# miniprot.net
KiCad netlist of a schematic drawn in EAGLE
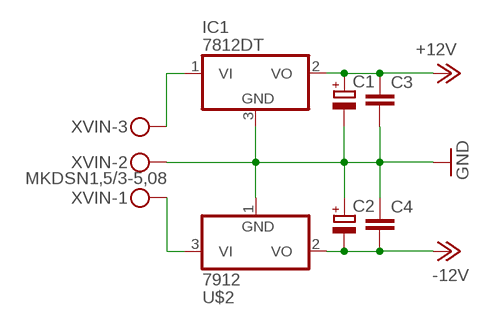
[diagram p0: schematic, sheet 1]
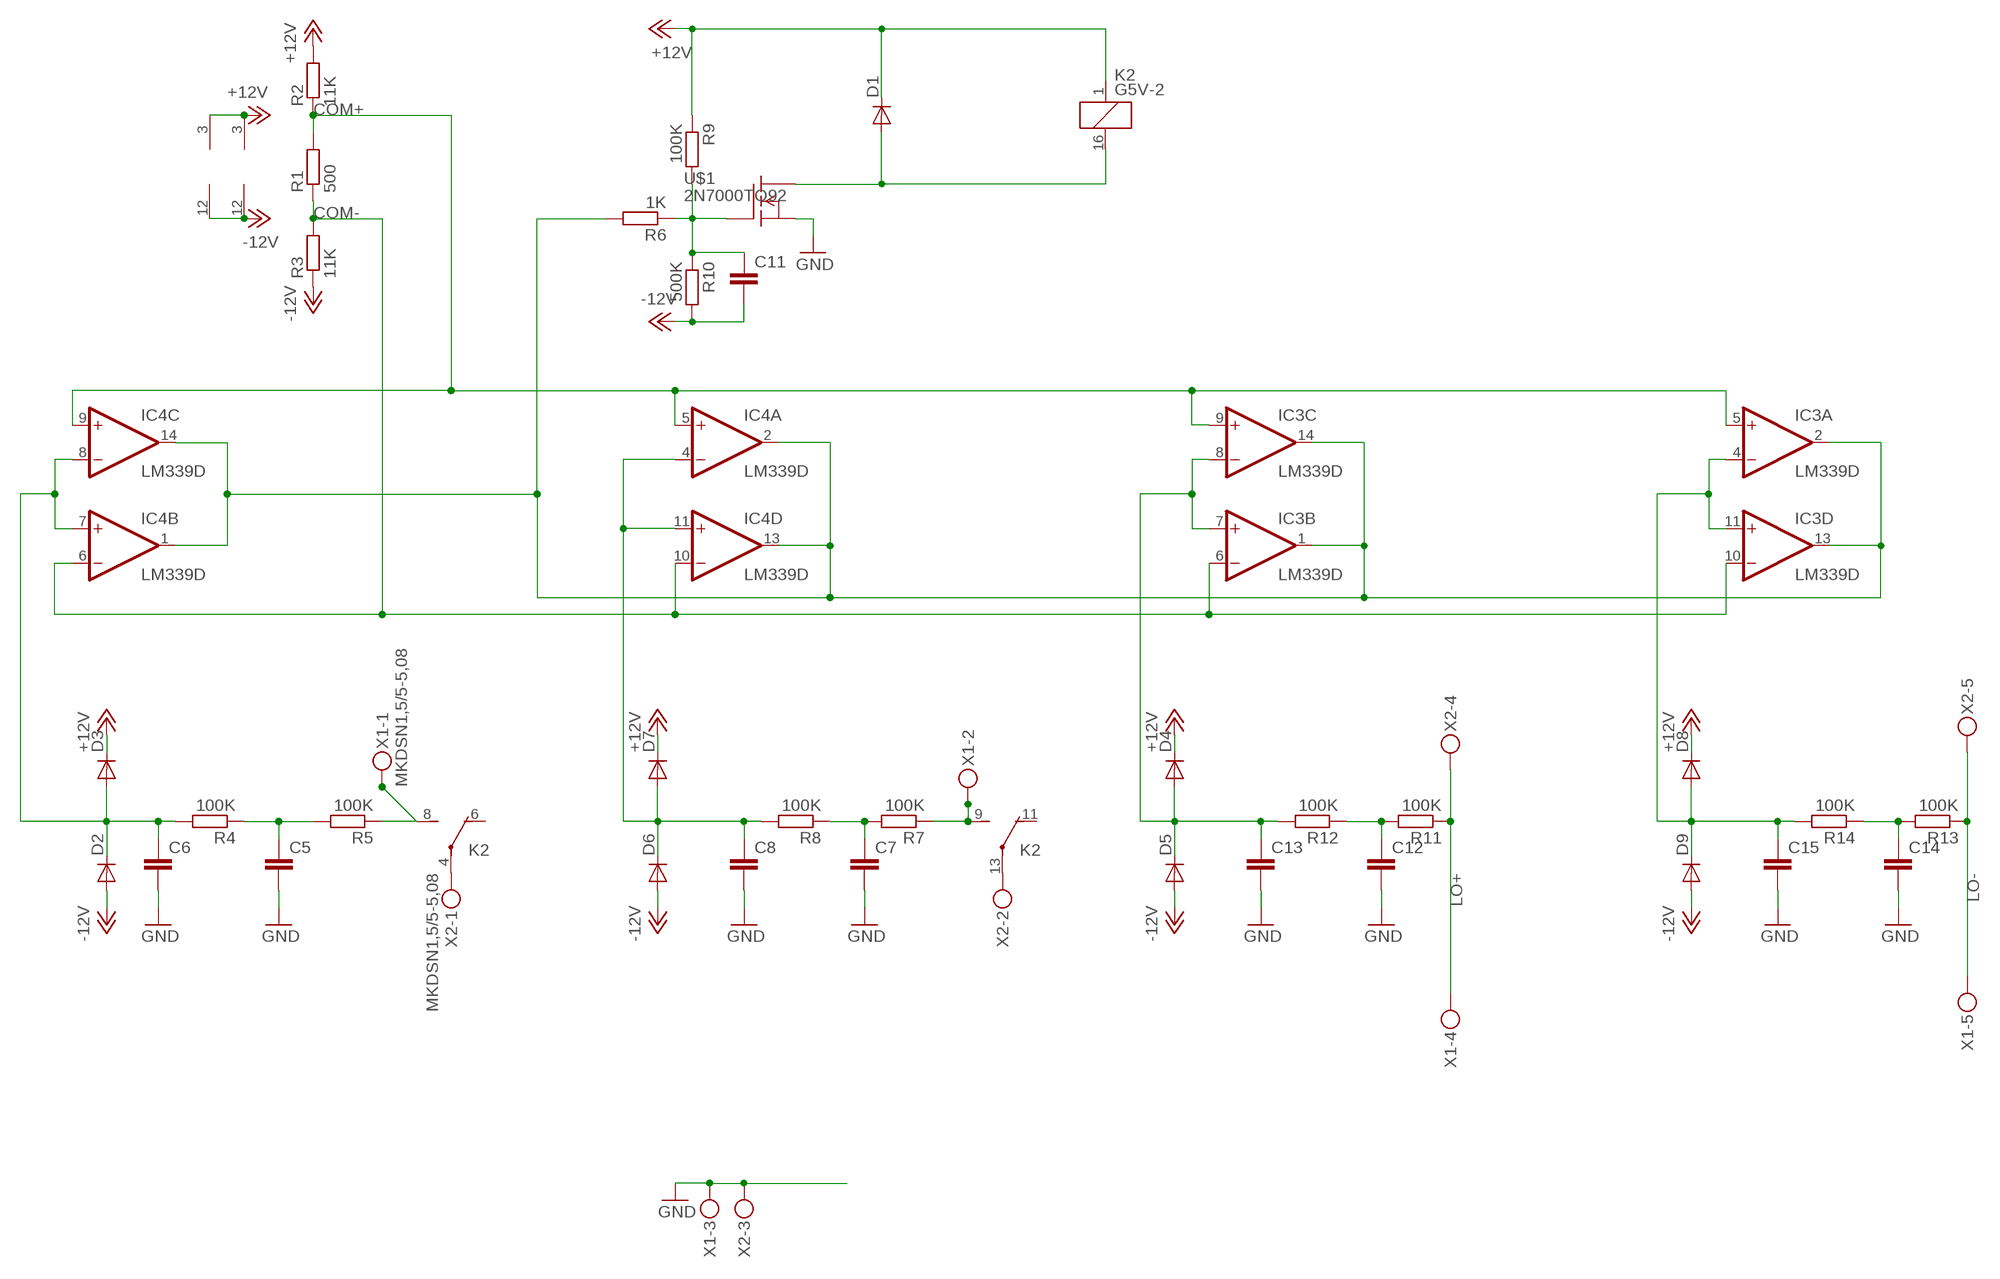
[diagram p1: schematic, sheet 2]

(export (version "E")
  (design (tool "Eeschema 10.0.6"))
  (components
    (comp (ref "C5")
      (value "C-EUC0805")
      (footprint "eagle-import:C0805")
      (libsource (lib "eagle-import") (part "C-EUC0805"))
    )
    (comp (ref "C6")
      (value "C-EUC0805")
      (footprint "eagle-import:C0805")
      (libsource (lib "eagle-import") (part "C-EUC0805"))
    )
    (comp (ref "C7")
      (value "C-EUC0805")
      (footprint "eagle-import:C0805")
      (libsource (lib "eagle-import") (part "C-EUC0805"))
    )
    (comp (ref "C8")
      (value "C-EUC0805")
      (footprint "eagle-import:C0805")
      (libsource (lib "eagle-import") (part "C-EUC0805"))
    )
    (comp (ref "C11")
      (value "C-EUC1210")
      (footprint "eagle-import:C1210")
      (libsource (lib "eagle-import") (part "C-EUC1210"))
    )
    (comp (ref "C12")
      (value "C-EUC0805")
      (footprint "eagle-import:C0805")
      (libsource (lib "eagle-import") (part "C-EUC0805"))
    )
    (comp (ref "C13")
      (value "C-EUC0805")
      (footprint "eagle-import:C0805")
      (libsource (lib "eagle-import") (part "C-EUC0805"))
    )
    (comp (ref "C14")
      (value "C-EUC0805")
      (footprint "eagle-import:C0805")
      (libsource (lib "eagle-import") (part "C-EUC0805"))
    )
    (comp (ref "C15")
      (value "C-EUC0805")
      (footprint "eagle-import:C0805")
      (libsource (lib "eagle-import") (part "C-EUC0805"))
    )
    (comp (ref "D1")
      (value "DIODE-DO214AC")
      (footprint "eagle-import:DO214AC")
      (libsource (lib "eagle-import") (part "DIODE-DO214AC"))
    )
    (comp (ref "D2")
      (value "DIODE-SOD80C")
      (footprint "eagle-import:SOD80C")
      (libsource (lib "eagle-import") (part "DIODE-SOD80C"))
    )
    (comp (ref "D3")
      (value "DIODE-SOD80C")
      (footprint "eagle-import:SOD80C")
      (libsource (lib "eagle-import") (part "DIODE-SOD80C"))
    )
    (comp (ref "D4")
      (value "DIODE-SOD80C")
      (footprint "eagle-import:SOD80C")
      (libsource (lib "eagle-import") (part "DIODE-SOD80C"))
    )
    (comp (ref "D5")
      (value "DIODE-SOD80C")
      (footprint "eagle-import:SOD80C")
      (libsource (lib "eagle-import") (part "DIODE-SOD80C"))
    )
    (comp (ref "D6")
      (value "DIODE-SOD80C")
      (footprint "eagle-import:SOD80C")
      (libsource (lib "eagle-import") (part "DIODE-SOD80C"))
    )
    (comp (ref "D7")
      (value "DIODE-SOD80C")
      (footprint "eagle-import:SOD80C")
      (libsource (lib "eagle-import") (part "DIODE-SOD80C"))
    )
    (comp (ref "D8")
      (value "DIODE-SOD80C")
      (footprint "eagle-import:SOD80C")
      (libsource (lib "eagle-import") (part "DIODE-SOD80C"))
    )
    (comp (ref "D9")
      (value "DIODE-SOD80C")
      (footprint "eagle-import:SOD80C")
      (libsource (lib "eagle-import") (part "DIODE-SOD80C"))
    )
    (comp (ref "IC3")
      (value "LM339D")
      (footprint "eagle-import:SO14")
      (libsource (lib "eagle-import") (part "LM339D"))
    )
    (comp (ref "IC4")
      (value "LM339D")
      (footprint "eagle-import:SO14")
      (libsource (lib "eagle-import") (part "linear_262_LM339D"))
    )
    (comp (ref "K2")
      (value "G5V-2")
      (footprint "eagle-import:G5V-2")
      (fields (field (name "MPN") "G5V-2 5DC"))
      (libsource (lib "eagle-import") (part "G5V-2"))
    )
    (comp (ref "R1")
      (value "500")
      (footprint "eagle-import:R0805")
      (libsource (lib "eagle-import") (part "R-EU_R0805"))
    )
    (comp (ref "R2")
      (value "11K")
      (footprint "eagle-import:R0805")
      (libsource (lib "eagle-import") (part "R-EU_R0805"))
    )
    (comp (ref "R3")
      (value "11K")
      (footprint "eagle-import:R0805")
      (libsource (lib "eagle-import") (part "R-EU_R0805"))
    )
    (comp (ref "R4")
      (value "100K")
      (footprint "eagle-import:R0805")
      (libsource (lib "eagle-import") (part "R-EU_R0805"))
    )
    (comp (ref "R5")
      (value "100K")
      (footprint "eagle-import:R0805")
      (libsource (lib "eagle-import") (part "R-EU_R0805"))
    )
    (comp (ref "R6")
      (value "1K")
      (footprint "eagle-import:R0805")
      (libsource (lib "eagle-import") (part "R-EU_R0805"))
    )
    (comp (ref "R7")
      (value "100K")
      (footprint "eagle-import:R0805")
      (libsource (lib "eagle-import") (part "R-EU_R0805"))
    )
    (comp (ref "R8")
      (value "100K")
      (footprint "eagle-import:R0805")
      (libsource (lib "eagle-import") (part "R-EU_R0805"))
    )
    (comp (ref "R9")
      (value "100K")
      (footprint "eagle-import:R0805")
      (libsource (lib "eagle-import") (part "R-EU_R0805"))
    )
    (comp (ref "R10")
      (value "500K")
      (footprint "eagle-import:R0805")
      (libsource (lib "eagle-import") (part "R-EU_R0805"))
    )
    (comp (ref "R11")
      (value "100K")
      (footprint "eagle-import:R0805")
      (libsource (lib "eagle-import") (part "R-EU_R0805"))
    )
    (comp (ref "R12")
      (value "100K")
      (footprint "eagle-import:R0805")
      (libsource (lib "eagle-import") (part "R-EU_R0805"))
    )
    (comp (ref "R13")
      (value "100K")
      (footprint "eagle-import:R0805")
      (libsource (lib "eagle-import") (part "R-EU_R0805"))
    )
    (comp (ref "R14")
      (value "100K")
      (footprint "eagle-import:R0805")
      (libsource (lib "eagle-import") (part "R-EU_R0805"))
    )
    (comp (ref "U$1")
      (value "2N7000TO92")
      (footprint "eagle-import:TO92-")
      (libsource (lib "eagle-import") (part "2N7000TO92"))
    )
    (comp (ref "X1")
      (value "MKDSN1,5/5-5,08")
      (footprint "eagle-import:MKDSN1,5_5-5,08")
      (libsource (lib "eagle-import") (part "MKDSN1,5/5-5,08"))
    )
    (comp (ref "X2")
      (value "MKDSN1,5/5-5,08")
      (footprint "eagle-import:MKDSN1,5_5-5,08")
      (libsource (lib "eagle-import") (part "MKDSN1,5/5-5,08"))
    )
    (comp (ref "C1")
      (value "CPOL-EUE2.5-7")
      (footprint "eagle-import:E2,5-7")
      (libsource (lib "eagle-import") (part "CPOL-EUE2.5-7"))
    )
    (comp (ref "C2")
      (value "CPOL-EUE2.5-7")
      (footprint "eagle-import:E2,5-7")
      (libsource (lib "eagle-import") (part "CPOL-EUE2.5-7"))
    )
    (comp (ref "C3")
      (value "C-EUC0805")
      (footprint "eagle-import:C0805")
      (libsource (lib "eagle-import") (part "C-EUC0805"))
    )
    (comp (ref "C4")
      (value "C-EUC0805")
      (footprint "eagle-import:C0805")
      (libsource (lib "eagle-import") (part "C-EUC0805"))
    )
    (comp (ref "IC1")
      (value "7812DT")
      (footprint "eagle-import:TO252")
      (libsource (lib "eagle-import") (part "78DT12"))
    )
    (comp (ref "U$2")
      (value "7912")
      (footprint "eagle-import:TO252")
      (libsource (lib "eagle-import") (part "7912"))
    )
    (comp (ref "XVIN")
      (value "MKDSN1,5/3-5,08")
      (footprint "eagle-import:MKDSN1,5_3-5,08")
      (libsource (lib "eagle-import") (part "MKDSN1,5/3-5,08"))
    )
  )
  (nets
    (net (code "1") (name "+12V") (class "Default")
      (node (ref "C1") (pin "+") (pinfunction "+_+") (pintype "passive"))
      (node (ref "C3") (pin "1") (pinfunction "1_1") (pintype "passive"))
      (node (ref "D1") (pin "C") (pinfunction "C_C") (pintype "passive"))
      (node (ref "D3") (pin "C") (pinfunction "C_C") (pintype "passive"))
      (node (ref "D4") (pin "C") (pinfunction "C_C") (pintype "passive"))
      (node (ref "D7") (pin "C") (pinfunction "C_C") (pintype "passive"))
      (node (ref "D8") (pin "C") (pinfunction "C_C") (pintype "passive"))
      (node (ref "IC1") (pin "2") (pinfunction "VO_2") (pintype "passive"))
      (node (ref "IC3") (pin "3") (pinfunction "V+_3") (pintype "power_in"))
      (node (ref "IC4") (pin "3") (pinfunction "V+_3") (pintype "power_in"))
      (node (ref "K2") (pin "1") (pinfunction "1_1") (pintype "passive"))
      (node (ref "R2") (pin "2") (pinfunction "2_2") (pintype "passive"))
      (node (ref "R9") (pin "1") (pinfunction "1_1") (pintype "passive"))
    )
    (net (code "2") (name "-12V") (class "Default")
      (node (ref "C11") (pin "2") (pinfunction "2_2") (pintype "passive"))
      (node (ref "C2") (pin "-") (pinfunction "-_-") (pintype "passive"))
      (node (ref "C4") (pin "2") (pinfunction "2_2") (pintype "passive"))
      (node (ref "D2") (pin "A") (pinfunction "A_A") (pintype "passive"))
      (node (ref "D5") (pin "A") (pinfunction "A_A") (pintype "passive"))
      (node (ref "D6") (pin "A") (pinfunction "A_A") (pintype "passive"))
      (node (ref "D9") (pin "A") (pinfunction "A_A") (pintype "passive"))
      (node (ref "IC3") (pin "12") (pinfunction "GND_12") (pintype "power_in"))
      (node (ref "IC4") (pin "12") (pinfunction "GND_12") (pintype "power_in"))
      (node (ref "R10") (pin "2") (pinfunction "2_2") (pintype "passive"))
      (node (ref "R3") (pin "1") (pinfunction "1_1") (pintype "passive"))
      (node (ref "U$2") (pin "2") (pinfunction "VO_2") (pintype "passive"))
    )
    (net (code "3") (name "COM+") (class "Default")
      (node (ref "IC3") (pin "5") (pinfunction "+IN_5") (pintype "input"))
      (node (ref "IC3") (pin "9") (pinfunction "+IN_9") (pintype "input"))
      (node (ref "IC4") (pin "5") (pinfunction "+IN_5") (pintype "input"))
      (node (ref "IC4") (pin "9") (pinfunction "+IN_9") (pintype "input"))
      (node (ref "R1") (pin "2") (pinfunction "2_2") (pintype "passive"))
      (node (ref "R2") (pin "1") (pinfunction "1_1") (pintype "passive"))
    )
    (net (code "4") (name "COM-") (class "Default")
      (node (ref "IC3") (pin "10") (pinfunction "-IN_10") (pintype "input"))
      (node (ref "IC3") (pin "6") (pinfunction "-IN_6") (pintype "input"))
      (node (ref "IC4") (pin "10") (pinfunction "-IN_10") (pintype "input"))
      (node (ref "IC4") (pin "6") (pinfunction "-IN_6") (pintype "input"))
      (node (ref "R1") (pin "1") (pinfunction "1_1") (pintype "passive"))
      (node (ref "R3") (pin "2") (pinfunction "2_2") (pintype "passive"))
    )
    (net (code "5") (name "GND") (class "Default")
      (node (ref "C1") (pin "-") (pinfunction "-_-") (pintype "passive"))
      (node (ref "C12") (pin "2") (pinfunction "2_2") (pintype "passive"))
      (node (ref "C13") (pin "2") (pinfunction "2_2") (pintype "passive"))
      (node (ref "C14") (pin "2") (pinfunction "2_2") (pintype "passive"))
      (node (ref "C15") (pin "2") (pinfunction "2_2") (pintype "passive"))
      (node (ref "C2") (pin "+") (pinfunction "+_+") (pintype "passive"))
      (node (ref "C3") (pin "2") (pinfunction "2_2") (pintype "passive"))
      (node (ref "C4") (pin "1") (pinfunction "1_1") (pintype "passive"))
      (node (ref "C5") (pin "2") (pinfunction "2_2") (pintype "passive"))
      (node (ref "C6") (pin "2") (pinfunction "2_2") (pintype "passive"))
      (node (ref "C7") (pin "2") (pinfunction "2_2") (pintype "passive"))
      (node (ref "C8") (pin "2") (pinfunction "2_2") (pintype "passive"))
      (node (ref "IC1") (pin "3") (pinfunction "GND_3") (pintype "passive"))
      (node (ref "U$1") (pin "3") (pinfunction "S_3") (pintype "passive"))
      (node (ref "U$2") (pin "1") (pinfunction "GND_1") (pintype "passive"))
      (node (ref "X1") (pin "3") (pinfunction "KL_3") (pintype "passive"))
      (node (ref "X2") (pin "3") (pinfunction "KL_3") (pintype "passive"))
      (node (ref "XVIN") (pin "2") (pinfunction "KL_2") (pintype "passive"))
    )
    (net (code "6") (name "LO+") (class "Default")
      (node (ref "R11") (pin "1") (pinfunction "1_1") (pintype "passive"))
      (node (ref "X1") (pin "4") (pinfunction "KL_4") (pintype "passive"))
      (node (ref "X2") (pin "4") (pinfunction "KL_4") (pintype "passive"))
    )
    (net (code "7") (name "LO-") (class "Default")
      (node (ref "R13") (pin "1") (pinfunction "1_1") (pintype "passive"))
      (node (ref "X1") (pin "5") (pinfunction "KL_5") (pintype "passive"))
      (node (ref "X2") (pin "5") (pinfunction "KL_5") (pintype "passive"))
    )
    (net (code "8") (name "Net-(C5-Pad1)") (class "Default")
      (node (ref "C5") (pin "1") (pinfunction "1_1") (pintype "passive"))
      (node (ref "R4") (pin "1") (pinfunction "1_1") (pintype "passive"))
      (node (ref "R5") (pin "2") (pinfunction "2_2") (pintype "passive"))
    )
    (net (code "9") (name "Net-(C7-Pad1)") (class "Default")
      (node (ref "C7") (pin "1") (pinfunction "1_1") (pintype "passive"))
      (node (ref "R7") (pin "2") (pinfunction "2_2") (pintype "passive"))
      (node (ref "R8") (pin "1") (pinfunction "1_1") (pintype "passive"))
    )
    (net (code "10") (name "Net-(C12-Pad1)") (class "Default")
      (node (ref "C12") (pin "1") (pinfunction "1_1") (pintype "passive"))
      (node (ref "R11") (pin "2") (pinfunction "2_2") (pintype "passive"))
      (node (ref "R12") (pin "1") (pinfunction "1_1") (pintype "passive"))
    )
    (net (code "11") (name "Net-(C14-Pad1)") (class "Default")
      (node (ref "C14") (pin "1") (pinfunction "1_1") (pintype "passive"))
      (node (ref "R13") (pin "2") (pinfunction "2_2") (pintype "passive"))
      (node (ref "R14") (pin "1") (pinfunction "1_1") (pintype "passive"))
    )
    (net (code "12") (name "Net-(IC1-VI)") (class "Default")
      (node (ref "IC1") (pin "1") (pinfunction "VI_1") (pintype "input"))
      (node (ref "XVIN") (pin "3") (pinfunction "KL_3") (pintype "passive"))
    )
    (net (code "13") (name "Net-(IC3A--IN)") (class "Default")
      (node (ref "C15") (pin "1") (pinfunction "1_1") (pintype "passive"))
      (node (ref "D8") (pin "A") (pinfunction "A_A") (pintype "passive"))
      (node (ref "D9") (pin "C") (pinfunction "C_C") (pintype "passive"))
      (node (ref "IC3") (pin "11") (pinfunction "+IN_11") (pintype "input"))
      (node (ref "IC3") (pin "4") (pinfunction "-IN_4") (pintype "input"))
      (node (ref "R14") (pin "2") (pinfunction "2_2") (pintype "passive"))
    )
    (net (code "14") (name "Net-(IC3A-OUT)") (class "Default")
      (node (ref "IC3") (pin "1") (pinfunction "OUT_1") (pintype "open_collector"))
      (node (ref "IC3") (pin "13") (pinfunction "OUT_13") (pintype "open_collector"))
      (node (ref "IC3") (pin "14") (pinfunction "OUT_14") (pintype "open_collector"))
      (node (ref "IC3") (pin "2") (pinfunction "OUT_2") (pintype "open_collector"))
      (node (ref "IC4") (pin "1") (pinfunction "OUT_1") (pintype "open_collector"))
      (node (ref "IC4") (pin "13") (pinfunction "OUT_13") (pintype "open_collector"))
      (node (ref "IC4") (pin "14") (pinfunction "OUT_14") (pintype "open_collector"))
      (node (ref "IC4") (pin "2") (pinfunction "OUT_2") (pintype "open_collector"))
      (node (ref "R6") (pin "2") (pinfunction "2_2") (pintype "passive"))
    )
    (net (code "15") (name "Net-(IC3B-+IN)") (class "Default")
      (node (ref "C13") (pin "1") (pinfunction "1_1") (pintype "passive"))
      (node (ref "D4") (pin "A") (pinfunction "A_A") (pintype "passive"))
      (node (ref "D5") (pin "C") (pinfunction "C_C") (pintype "passive"))
      (node (ref "IC3") (pin "7") (pinfunction "+IN_7") (pintype "input"))
      (node (ref "IC3") (pin "8") (pinfunction "-IN_8") (pintype "input"))
      (node (ref "R12") (pin "2") (pinfunction "2_2") (pintype "passive"))
    )
    (net (code "16") (name "Net-(IC4A--IN)") (class "Default")
      (node (ref "C8") (pin "1") (pinfunction "1_1") (pintype "passive"))
      (node (ref "D6") (pin "C") (pinfunction "C_C") (pintype "passive"))
      (node (ref "D7") (pin "A") (pinfunction "A_A") (pintype "passive"))
      (node (ref "IC4") (pin "11") (pinfunction "+IN_11") (pintype "input"))
      (node (ref "IC4") (pin "4") (pinfunction "-IN_4") (pintype "input"))
      (node (ref "R8") (pin "2") (pinfunction "2_2") (pintype "passive"))
    )
    (net (code "17") (name "Net-(IC4B-+IN)") (class "Default")
      (node (ref "C6") (pin "1") (pinfunction "1_1") (pintype "passive"))
      (node (ref "D2") (pin "C") (pinfunction "C_C") (pintype "passive"))
      (node (ref "D3") (pin "A") (pinfunction "A_A") (pintype "passive"))
      (node (ref "IC4") (pin "7") (pinfunction "+IN_7") (pintype "input"))
      (node (ref "IC4") (pin "8") (pinfunction "-IN_8") (pintype "input"))
      (node (ref "R4") (pin "2") (pinfunction "2_2") (pintype "passive"))
    )
    (net (code "18") (name "Net-(K2A-P)") (class "Default")
      (node (ref "K2") (pin "4") (pinfunction "P_4") (pintype "passive"))
      (node (ref "X2") (pin "1") (pinfunction "KL_1") (pintype "passive"))
    )
    (net (code "19") (name "Net-(K2A-S)") (class "Default")
      (node (ref "K2") (pin "8") (pinfunction "S_8") (pintype "passive"))
      (node (ref "R5") (pin "1") (pinfunction "1_1") (pintype "passive"))
      (node (ref "X1") (pin "1") (pinfunction "KL_1") (pintype "passive"))
    )
    (net (code "20") (name "Net-(K2B-P)") (class "Default")
      (node (ref "K2") (pin "13") (pinfunction "P_13") (pintype "passive"))
      (node (ref "X2") (pin "2") (pinfunction "KL_2") (pintype "passive"))
    )
    (net (code "21") (name "Net-(K2B-S)") (class "Default")
      (node (ref "K2") (pin "9") (pinfunction "S_9") (pintype "passive"))
      (node (ref "R7") (pin "1") (pinfunction "1_1") (pintype "passive"))
      (node (ref "X1") (pin "2") (pinfunction "KL_2") (pintype "passive"))
    )
    (net (code "22") (name "Net-(K2C-2)") (class "Default")
      (node (ref "D1") (pin "A") (pinfunction "A_A") (pintype "passive"))
      (node (ref "K2") (pin "16") (pinfunction "2_16") (pintype "passive"))
      (node (ref "U$1") (pin "1") (pinfunction "D_1") (pintype "passive"))
    )
    (net (code "23") (name "Net-(U$1-G)") (class "Default")
      (node (ref "C11") (pin "1") (pinfunction "1_1") (pintype "passive"))
      (node (ref "R10") (pin "1") (pinfunction "1_1") (pintype "passive"))
      (node (ref "R6") (pin "1") (pinfunction "1_1") (pintype "passive"))
      (node (ref "R9") (pin "2") (pinfunction "2_2") (pintype "passive"))
      (node (ref "U$1") (pin "2") (pinfunction "G_2") (pintype "passive"))
    )
    (net (code "24") (name "Net-(U$2-VI)") (class "Default")
      (node (ref "U$2") (pin "3") (pinfunction "VI_3") (pintype "input"))
      (node (ref "XVIN") (pin "1") (pinfunction "KL_1") (pintype "passive"))
    )
    (net (code "25") (name "unconnected-(K2A-O-Pad6)") (class "Default")
      (node (ref "K2") (pin "6") (pinfunction "O_6") (pintype "passive"))
    )
    (net (code "26") (name "unconnected-(K2B-O-Pad11)") (class "Default")
      (node (ref "K2") (pin "11") (pinfunction "O_11") (pintype "passive"))
    )
  )
)
